# proper.net
KiCad netlist of a schematic drawn in EAGLE
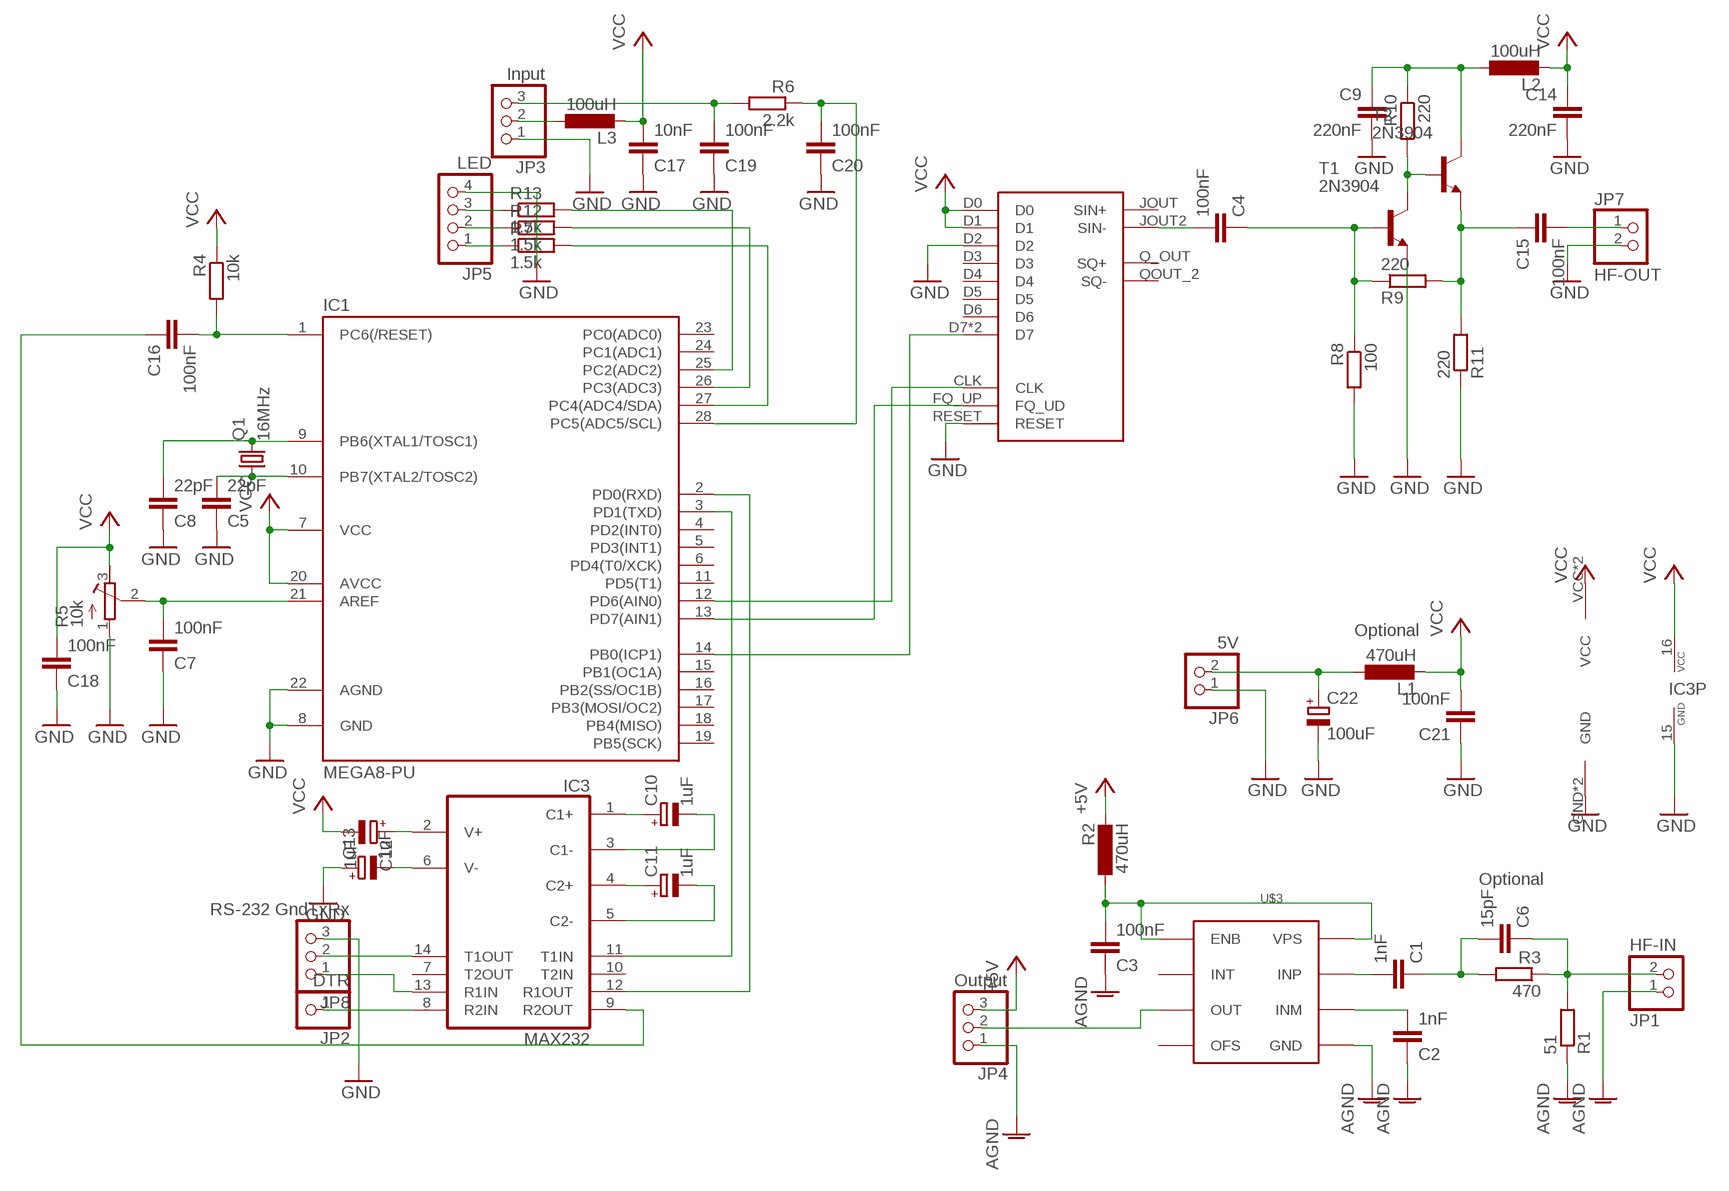
[diagram p0: schematic, sheet 1]

(export (version "E")
  (design (tool "Eeschema 10.0.6"))
  (components
    (comp (ref "C1")
      (value "1nF")
      (footprint "eagle-import:C025-025X050")
      (libsource (lib "eagle-import") (part "C-EU025-025X050"))
    )
    (comp (ref "C2")
      (value "1nF")
      (footprint "eagle-import:C025-025X050")
      (libsource (lib "eagle-import") (part "C-EU025-025X050"))
    )
    (comp (ref "C3")
      (value "100nF")
      (footprint "eagle-import:C025-025X050")
      (libsource (lib "eagle-import") (part "C-EU025-025X050"))
    )
    (comp (ref "C4")
      (value "100nF")
      (footprint "eagle-import:C025-025X050")
      (libsource (lib "eagle-import") (part "C-EU025-025X050"))
    )
    (comp (ref "C5")
      (value "22pF")
      (footprint "eagle-import:C102-043X133")
      (libsource (lib "eagle-import") (part "C-EU102-043X133"))
    )
    (comp (ref "C6")
      (value "15pF")
      (footprint "eagle-import:C050-025X075")
      (libsource (lib "eagle-import") (part "C-EU050-025X075"))
    )
    (comp (ref "C7")
      (value "100nF")
      (footprint "eagle-import:C025-025X050")
      (libsource (lib "eagle-import") (part "C-EU025-025X050"))
    )
    (comp (ref "C8")
      (value "22pF")
      (footprint "eagle-import:C025-025X050")
      (libsource (lib "eagle-import") (part "C-EU025-025X050"))
    )
    (comp (ref "C9")
      (value "220nF")
      (footprint "eagle-import:C025-025X050")
      (libsource (lib "eagle-import") (part "C-EU025-025X050"))
    )
    (comp (ref "C10")
      (value "1uF")
      (footprint "eagle-import:E2,5-5")
      (libsource (lib "eagle-import") (part "CPOL-EUE2.5-5"))
    )
    (comp (ref "C11")
      (value "1uF")
      (footprint "eagle-import:E2,5-5")
      (libsource (lib "eagle-import") (part "CPOL-EUE2.5-5"))
    )
    (comp (ref "C12")
      (value "1uF")
      (footprint "eagle-import:E2,5-5")
      (libsource (lib "eagle-import") (part "CPOL-EUE2.5-5"))
    )
    (comp (ref "C13")
      (value "1uF")
      (footprint "eagle-import:E2,5-5")
      (libsource (lib "eagle-import") (part "CPOL-EUE2.5-5"))
    )
    (comp (ref "C14")
      (value "220nF")
      (footprint "eagle-import:C050-025X075")
      (libsource (lib "eagle-import") (part "C-EU050-025X075"))
    )
    (comp (ref "C15")
      (value "100nF")
      (footprint "eagle-import:C050-025X075")
      (libsource (lib "eagle-import") (part "C-EU050-025X075"))
    )
    (comp (ref "C16")
      (value "100nF")
      (footprint "eagle-import:C075-032X103")
      (libsource (lib "eagle-import") (part "C-EU075-032X103"))
    )
    (comp (ref "C17")
      (value "10nF")
      (footprint "eagle-import:C025-025X050")
      (libsource (lib "eagle-import") (part "C-EU025-025X050"))
    )
    (comp (ref "C18")
      (value "100nF")
      (footprint "eagle-import:C050-025X075")
      (libsource (lib "eagle-import") (part "C-EU050-025X075"))
    )
    (comp (ref "C19")
      (value "100nF")
      (footprint "eagle-import:C025-025X050")
      (libsource (lib "eagle-import") (part "C-EU025-025X050"))
    )
    (comp (ref "C20")
      (value "100nF")
      (footprint "eagle-import:C025-025X050")
      (libsource (lib "eagle-import") (part "C-EU025-025X050"))
    )
    (comp (ref "C21")
      (value "100nF")
      (footprint "eagle-import:C025-025X050")
      (libsource (lib "eagle-import") (part "C-EU025-025X050"))
    )
    (comp (ref "C22")
      (value "100uF")
      (footprint "eagle-import:E2,5-6")
      (libsource (lib "eagle-import") (part "CPOL-EUE2.5-6"))
    )
    (comp (ref "IC1")
      (value "MEGA8-PU")
      (footprint "eagle-import:DIL28-3")
      (libsource (lib "eagle-import") (part "MEGA8-PU"))
    )
    (comp (ref "IC3")
      (value "MAX232")
      (footprint "eagle-import:DIL16")
      (fields (field (name "MF") "MAXIM") (field (name "MPN") "MAX232ACPE+"))
      (libsource (lib "eagle-import") (part "MAX232"))
    )
    (comp (ref "JP1")
      (value "HF-IN")
      (footprint "eagle-import:1X02")
      (libsource (lib "eagle-import") (part "PINHD-1X2"))
    )
    (comp (ref "JP2")
      (value "DTR")
      (footprint "eagle-import:1X01")
      (libsource (lib "eagle-import") (part "PINHD-1X1"))
    )
    (comp (ref "JP3")
      (value "Input")
      (footprint "eagle-import:1X03")
      (libsource (lib "eagle-import") (part "PINHD-1X3"))
    )
    (comp (ref "JP4")
      (value "Output")
      (footprint "eagle-import:1X03")
      (libsource (lib "eagle-import") (part "PINHD-1X3"))
    )
    (comp (ref "JP5")
      (value "LED")
      (footprint "eagle-import:1X04")
      (libsource (lib "eagle-import") (part "PINHD-1X4"))
    )
    (comp (ref "JP6")
      (value "5V")
      (footprint "eagle-import:1X02")
      (libsource (lib "eagle-import") (part "PINHD-1X2"))
    )
    (comp (ref "JP7")
      (value "HF-OUT")
      (footprint "eagle-import:1X02")
      (libsource (lib "eagle-import") (part "PINHD-1X2"))
    )
    (comp (ref "JP8")
      (value "RS-232 GndTxRx")
      (footprint "eagle-import:1X03")
      (libsource (lib "eagle-import") (part "PINHD-1X3"))
    )
    (comp (ref "L1")
      (value "470uH")
      (footprint "eagle-import:0207_5V")
      (libsource (lib "eagle-import") (part "L-EU0207/5V"))
    )
    (comp (ref "L2")
      (value "100uH")
      (footprint "eagle-import:0207_12")
      (libsource (lib "eagle-import") (part "L-EU0207/12"))
    )
    (comp (ref "L3")
      (value "100uH")
      (footprint "eagle-import:0207_2V")
      (libsource (lib "eagle-import") (part "L-EU0207/2V"))
    )
    (comp (ref "Q1")
      (value "16MHz")
      (footprint "eagle-import:HC49U-V")
      (libsource (lib "eagle-import") (part "CRYSTALHC49U-V"))
    )
    (comp (ref "R1")
      (value "51")
      (footprint "eagle-import:0204V")
      (libsource (lib "eagle-import") (part "R-EU_0204/2V"))
    )
    (comp (ref "R2")
      (value "470uH")
      (footprint "eagle-import:0204_5")
      (libsource (lib "eagle-import") (part "L-EU0204/5"))
    )
    (comp (ref "R3")
      (value "470")
      (footprint "eagle-import:0204_5")
      (libsource (lib "eagle-import") (part "R-EU_0204/5"))
    )
    (comp (ref "R4")
      (value "10k")
      (footprint "eagle-import:0204_5")
      (libsource (lib "eagle-import") (part "R-EU_0204/5"))
    )
    (comp (ref "R5")
      (value "10k")
      (footprint "eagle-import:RTRIM64W")
      (libsource (lib "eagle-import") (part "R-TRIMM64W"))
    )
    (comp (ref "R6")
      (value "2.2k")
      (footprint "eagle-import:0204V")
      (libsource (lib "eagle-import") (part "R-EU_0204/2V"))
    )
    (comp (ref "R7")
      (value "1.5k")
      (footprint "eagle-import:0204_5")
      (libsource (lib "eagle-import") (part "R-EU_0204/5"))
    )
    (comp (ref "R8")
      (value "100")
      (footprint "eagle-import:0204V")
      (libsource (lib "eagle-import") (part "R-EU_0204/2V"))
    )
    (comp (ref "R9")
      (value "220")
      (footprint "eagle-import:0204V")
      (libsource (lib "eagle-import") (part "R-EU_0204/2V"))
    )
    (comp (ref "R10")
      (value "220")
      (footprint "eagle-import:0204V")
      (libsource (lib "eagle-import") (part "R-EU_0204/2V"))
    )
    (comp (ref "R11")
      (value "220")
      (footprint "eagle-import:0204V")
      (libsource (lib "eagle-import") (part "R-EU_0204/2V"))
    )
    (comp (ref "R12")
      (value "1.5k")
      (footprint "eagle-import:0204_5")
      (libsource (lib "eagle-import") (part "R-EU_0204/5"))
    )
    (comp (ref "R13")
      (value "1.5k")
      (footprint "eagle-import:0204_5")
      (libsource (lib "eagle-import") (part "R-EU_0204/5"))
    )
    (comp (ref "T1")
      (value "2N3904")
      (footprint "eagle-import:TO92-EBC")
      (libsource (lib "eagle-import") (part "-NPN-TO92-EBC2N3904"))
    )
    (comp (ref "T2")
      (value "2N3904")
      (footprint "eagle-import:TO92-EBC")
      (libsource (lib "eagle-import") (part "-NPN-TO92-EBC2N3904"))
    )
    (comp (ref "U$1")
      (value "DDS-1")
      (footprint "eagle-import:DDS-1")
      (libsource (lib "eagle-import") (part "DDS-1"))
    )
    (comp (ref "U$3")
      (value "AD8307")
      (footprint "eagle-import:DIL08")
      (libsource (lib "eagle-import") (part "AD8307"))
    )
  )
  (nets
    (net (code "1") (name "+5V") (class "Default")
      (node (ref "JP4") (pin "3") (pinfunction "3_3") (pintype "passive"))
      (node (ref "R2") (pin "2") (pinfunction "2_2") (pintype "passive"))
    )
    (net (code "2") (name "AGND") (class "Default")
      (node (ref "C2") (pin "1") (pinfunction "1_1") (pintype "passive"))
      (node (ref "C3") (pin "1") (pinfunction "1_1") (pintype "passive"))
      (node (ref "JP1") (pin "1") (pinfunction "1_1") (pintype "passive"))
      (node (ref "JP4") (pin "1") (pinfunction "1_1") (pintype "passive"))
      (node (ref "R1") (pin "1") (pinfunction "1_1") (pintype "passive"))
      (node (ref "U$3") (pin "2") (pinfunction "GND_2") (pintype "bidirectional"))
    )
    (net (code "3") (name "GND") (class "Default")
      (node (ref "C13") (pin "+") (pinfunction "+_+") (pintype "passive"))
      (node (ref "C14") (pin "2") (pinfunction "2_2") (pintype "passive"))
      (node (ref "C17") (pin "1") (pinfunction "1_1") (pintype "passive"))
      (node (ref "C18") (pin "1") (pinfunction "1_1") (pintype "passive"))
      (node (ref "C19") (pin "1") (pinfunction "1_1") (pintype "passive"))
      (node (ref "C20") (pin "1") (pinfunction "1_1") (pintype "passive"))
      (node (ref "C21") (pin "1") (pinfunction "1_1") (pintype "passive"))
      (node (ref "C22") (pin "-") (pinfunction "-_-") (pintype "passive"))
      (node (ref "C5") (pin "1") (pinfunction "1_1") (pintype "passive"))
      (node (ref "C7") (pin "1") (pinfunction "1_1") (pintype "passive"))
      (node (ref "C8") (pin "1") (pinfunction "1_1") (pintype "passive"))
      (node (ref "C9") (pin "2") (pinfunction "2_2") (pintype "passive"))
      (node (ref "IC1") (pin "22") (pinfunction "AGND_22") (pintype "power_in"))
      (node (ref "IC1") (pin "8") (pinfunction "GND_8") (pintype "power_in"))
      (node (ref "IC3") (pin "15") (pinfunction "GND_15") (pintype "power_in"))
      (node (ref "JP3") (pin "1") (pinfunction "1_1") (pintype "passive"))
      (node (ref "JP5") (pin "4") (pinfunction "4_4") (pintype "passive"))
      (node (ref "JP6") (pin "1") (pinfunction "1_1") (pintype "passive"))
      (node (ref "JP7") (pin "2") (pinfunction "2_2") (pintype "passive"))
      (node (ref "JP8") (pin "3") (pinfunction "3_3") (pintype "passive"))
      (node (ref "R11") (pin "1") (pinfunction "1_1") (pintype "passive"))
      (node (ref "R5") (pin "1") (pinfunction "A_1") (pintype "passive"))
      (node (ref "R8") (pin "2") (pinfunction "2_2") (pintype "passive"))
      (node (ref "T1") (pin "E") (pinfunction "E_E") (pintype "passive"))
      (node (ref "U$1") (pin "D2") (pinfunction "D2_D2") (pintype "bidirectional"))
      (node (ref "U$1") (pin "GND") (pinfunction "GND_GND") (pintype "bidirectional"))
      (node (ref "U$1") (pin "GND2") (pinfunction "GND_GND2") (pintype "bidirectional"))
      (node (ref "U$1") (pin "RESET") (pinfunction "RESET_RESET") (pintype "bidirectional"))
    )
    (net (code "4") (name "Net-(C1-Pad1)") (class "Default")
      (node (ref "C1") (pin "1") (pinfunction "1_1") (pintype "passive"))
      (node (ref "C6") (pin "2") (pinfunction "2_2") (pintype "passive"))
      (node (ref "R3") (pin "2") (pinfunction "2_2") (pintype "passive"))
    )
    (net (code "5") (name "Net-(C4-Pad1)") (class "Default")
      (node (ref "C4") (pin "1") (pinfunction "1_1") (pintype "passive"))
      (node (ref "R8") (pin "1") (pinfunction "1_1") (pintype "passive"))
      (node (ref "R9") (pin "1") (pinfunction "1_1") (pintype "passive"))
      (node (ref "T1") (pin "B") (pinfunction "B_B") (pintype "passive"))
    )
    (net (code "6") (name "Net-(C6-Pad1)") (class "Default")
      (node (ref "C6") (pin "1") (pinfunction "1_1") (pintype "passive"))
      (node (ref "JP1") (pin "2") (pinfunction "2_2") (pintype "passive"))
      (node (ref "R1") (pin "2") (pinfunction "2_2") (pintype "passive"))
      (node (ref "R3") (pin "1") (pinfunction "1_1") (pintype "passive"))
    )
    (net (code "7") (name "Net-(C9-Pad1)") (class "Default")
      (node (ref "C9") (pin "1") (pinfunction "1_1") (pintype "passive"))
      (node (ref "L2") (pin "1") (pinfunction "1_1") (pintype "passive"))
      (node (ref "R10") (pin "1") (pinfunction "1_1") (pintype "passive"))
      (node (ref "T2") (pin "C") (pinfunction "C_C") (pintype "passive"))
    )
    (net (code "8") (name "Net-(C15-Pad1)") (class "Default")
      (node (ref "C15") (pin "1") (pinfunction "1_1") (pintype "passive"))
      (node (ref "R11") (pin "2") (pinfunction "2_2") (pintype "passive"))
      (node (ref "R9") (pin "2") (pinfunction "2_2") (pintype "passive"))
      (node (ref "T2") (pin "E") (pinfunction "E_E") (pintype "passive"))
    )
    (net (code "9") (name "Net-(C15-Pad2)") (class "Default")
      (node (ref "C15") (pin "2") (pinfunction "2_2") (pintype "passive"))
      (node (ref "JP7") (pin "1") (pinfunction "1_1") (pintype "passive"))
    )
    (net (code "10") (name "Net-(C19-Pad2)") (class "Default")
      (node (ref "C19") (pin "2") (pinfunction "2_2") (pintype "passive"))
      (node (ref "JP3") (pin "3") (pinfunction "3_3") (pintype "passive"))
      (node (ref "R6") (pin "2") (pinfunction "2_2") (pintype "passive"))
    )
    (net (code "11") (name "Net-(C22-Pad+)") (class "Default")
      (node (ref "C22") (pin "+") (pinfunction "+_+") (pintype "passive"))
      (node (ref "JP6") (pin "2") (pinfunction "2_2") (pintype "passive"))
      (node (ref "L1") (pin "1") (pinfunction "1_1") (pintype "passive"))
    )
    (net (code "12") (name "Net-(IC1-AREF)") (class "Default")
      (node (ref "C7") (pin "2") (pinfunction "2_2") (pintype "passive"))
      (node (ref "IC1") (pin "21") (pinfunction "AREF_21") (pintype "passive"))
      (node (ref "R5") (pin "2") (pinfunction "S_2") (pintype "passive"))
    )
    (net (code "13") (name "Net-(IC1-PB0(ICP1))") (class "Default")
      (node (ref "IC1") (pin "14") (pinfunction "PB0(ICP1)_14") (pintype "bidirectional"))
      (node (ref "U$1") (pin "D7") (pinfunction "D7_D7") (pintype "bidirectional"))
      (node (ref "U$1") (pin "D7_2") (pinfunction "D7_D7_2") (pintype "bidirectional"))
    )
    (net (code "14") (name "Net-(IC1-PB6(XTAL1{slash}TOSC1))") (class "Default")
      (node (ref "C8") (pin "2") (pinfunction "2_2") (pintype "passive"))
      (node (ref "IC1") (pin "9") (pinfunction "PB6(XTAL1/TOSC1)_9") (pintype "bidirectional"))
      (node (ref "Q1") (pin "2") (pinfunction "2_2") (pintype "passive"))
    )
    (net (code "15") (name "Net-(IC1-PB7(XTAL2{slash}TOSC2))") (class "Default")
      (node (ref "C5") (pin "2") (pinfunction "2_2") (pintype "passive"))
      (node (ref "IC1") (pin "10") (pinfunction "PB7(XTAL2/TOSC2)_10") (pintype "bidirectional"))
      (node (ref "Q1") (pin "1") (pinfunction "1_1") (pintype "passive"))
    )
    (net (code "16") (name "Net-(IC1-PC2(ADC2))") (class "Default")
      (node (ref "IC1") (pin "25") (pinfunction "PC2(ADC2)_25") (pintype "bidirectional"))
      (node (ref "R13") (pin "2") (pinfunction "2_2") (pintype "passive"))
    )
    (net (code "17") (name "Net-(IC1-PC3(ADC3))") (class "Default")
      (node (ref "IC1") (pin "26") (pinfunction "PC3(ADC3)_26") (pintype "bidirectional"))
      (node (ref "R12") (pin "2") (pinfunction "2_2") (pintype "passive"))
    )
    (net (code "18") (name "Net-(IC1-PC4(ADC4{slash}SDA))") (class "Default")
      (node (ref "IC1") (pin "27") (pinfunction "PC4(ADC4/SDA)_27") (pintype "bidirectional"))
      (node (ref "R7") (pin "2") (pinfunction "2_2") (pintype "passive"))
    )
    (net (code "19") (name "Net-(IC1-PC5(ADC5{slash}SCL))") (class "Default")
      (node (ref "C20") (pin "2") (pinfunction "2_2") (pintype "passive"))
      (node (ref "IC1") (pin "28") (pinfunction "PC5(ADC5/SCL)_28") (pintype "bidirectional"))
      (node (ref "R6") (pin "1") (pinfunction "1_1") (pintype "passive"))
    )
    (net (code "20") (name "Net-(IC1-PC6({slash}RESET))") (class "Default")
      (node (ref "C16") (pin "2") (pinfunction "2_2") (pintype "passive"))
      (node (ref "IC1") (pin "1") (pinfunction "PC6(/RESET)_1") (pintype "bidirectional"))
      (node (ref "R4") (pin "2") (pinfunction "2_2") (pintype "passive"))
    )
    (net (code "21") (name "Net-(IC1-PD0(RXD))") (class "Default")
      (node (ref "IC1") (pin "2") (pinfunction "PD0(RXD)_2") (pintype "bidirectional"))
      (node (ref "IC3") (pin "12") (pinfunction "R1OUT_12") (pintype "output"))
    )
    (net (code "22") (name "Net-(IC1-PD1(TXD))") (class "Default")
      (node (ref "IC1") (pin "3") (pinfunction "PD1(TXD)_3") (pintype "bidirectional"))
      (node (ref "IC3") (pin "11") (pinfunction "T1IN_11") (pintype "input"))
    )
    (net (code "23") (name "Net-(IC1-PD6(AIN0))") (class "Default")
      (node (ref "IC1") (pin "12") (pinfunction "PD6(AIN0)_12") (pintype "bidirectional"))
      (node (ref "U$1") (pin "CLK") (pinfunction "CLK_CLK") (pintype "bidirectional"))
    )
    (net (code "24") (name "Net-(IC1-PD7(AIN1))") (class "Default")
      (node (ref "IC1") (pin "13") (pinfunction "PD7(AIN1)_13") (pintype "bidirectional"))
      (node (ref "U$1") (pin "FQ_UP") (pinfunction "FQ_UD_FQ_UP") (pintype "bidirectional"))
    )
    (net (code "25") (name "Net-(IC3A-C1+)") (class "Default")
      (node (ref "C10") (pin "+") (pinfunction "+_+") (pintype "passive"))
      (node (ref "IC3") (pin "1") (pinfunction "C1+_1") (pintype "bidirectional"))
    )
    (net (code "26") (name "Net-(IC3A-C1-)") (class "Default")
      (node (ref "C10") (pin "-") (pinfunction "-_-") (pintype "passive"))
      (node (ref "IC3") (pin "3") (pinfunction "C1-_3") (pintype "bidirectional"))
    )
    (net (code "27") (name "Net-(IC3A-C2+)") (class "Default")
      (node (ref "C11") (pin "+") (pinfunction "+_+") (pintype "passive"))
      (node (ref "IC3") (pin "4") (pinfunction "C2+_4") (pintype "bidirectional"))
    )
    (net (code "28") (name "Net-(IC3A-C2-)") (class "Default")
      (node (ref "C11") (pin "-") (pinfunction "-_-") (pintype "passive"))
      (node (ref "IC3") (pin "5") (pinfunction "C2-_5") (pintype "bidirectional"))
    )
    (net (code "29") (name "Net-(IC3A-R1IN)") (class "Default")
      (node (ref "IC3") (pin "13") (pinfunction "R1IN_13") (pintype "input"))
      (node (ref "JP8") (pin "1") (pinfunction "1_1") (pintype "passive"))
    )
    (net (code "30") (name "Net-(IC3A-R2IN)") (class "Default")
      (node (ref "IC3") (pin "8") (pinfunction "R2IN_8") (pintype "input"))
      (node (ref "JP2") (pin "1") (pinfunction "1_1") (pintype "passive"))
    )
    (net (code "31") (name "Net-(IC3A-R2OUT)") (class "Default")
      (node (ref "C16") (pin "1") (pinfunction "1_1") (pintype "passive"))
      (node (ref "IC3") (pin "9") (pinfunction "R2OUT_9") (pintype "output"))
    )
    (net (code "32") (name "Net-(IC3A-T1OUT)") (class "Default")
      (node (ref "IC3") (pin "14") (pinfunction "T1OUT_14") (pintype "output"))
      (node (ref "JP8") (pin "2") (pinfunction "2_2") (pintype "passive"))
    )
    (net (code "33") (name "Net-(IC3A-V+)") (class "Default")
      (node (ref "C12") (pin "+") (pinfunction "+_+") (pintype "passive"))
      (node (ref "IC3") (pin "2") (pinfunction "V+_2") (pintype "bidirectional"))
    )
    (net (code "34") (name "Net-(IC3A-V-)") (class "Default")
      (node (ref "C13") (pin "-") (pinfunction "-_-") (pintype "passive"))
      (node (ref "IC3") (pin "6") (pinfunction "V-_6") (pintype "bidirectional"))
    )
    (net (code "35") (name "Net-(JP3-Pad2)") (class "Default")
      (node (ref "JP3") (pin "2") (pinfunction "2_2") (pintype "passive"))
      (node (ref "L3") (pin "1") (pinfunction "1_1") (pintype "passive"))
    )
    (net (code "36") (name "Net-(JP5-Pad1)") (class "Default")
      (node (ref "JP5") (pin "1") (pinfunction "1_1") (pintype "passive"))
      (node (ref "R7") (pin "1") (pinfunction "1_1") (pintype "passive"))
    )
    (net (code "37") (name "Net-(JP5-Pad2)") (class "Default")
      (node (ref "JP5") (pin "2") (pinfunction "2_2") (pintype "passive"))
      (node (ref "R12") (pin "1") (pinfunction "1_1") (pintype "passive"))
    )
    (net (code "38") (name "Net-(JP5-Pad3)") (class "Default")
      (node (ref "JP5") (pin "3") (pinfunction "3_3") (pintype "passive"))
      (node (ref "R13") (pin "1") (pinfunction "1_1") (pintype "passive"))
    )
    (net (code "39") (name "Net-(R10-Pad2)") (class "Default")
      (node (ref "R10") (pin "2") (pinfunction "2_2") (pintype "passive"))
      (node (ref "T1") (pin "C") (pinfunction "C_C") (pintype "passive"))
      (node (ref "T2") (pin "B") (pinfunction "B_B") (pintype "passive"))
    )
    (net (code "40") (name "Net-(U$1A-SIN-)") (class "Default")
      (node (ref "C4") (pin "2") (pinfunction "2_2") (pintype "passive"))
      (node (ref "U$1") (pin "JOUT2") (pinfunction "SIN-_JOUT2") (pintype "bidirectional"))
    )
    (net (code "41") (name "Net-(U$3-ENB)") (class "Default")
      (node (ref "C3") (pin "2") (pinfunction "2_2") (pintype "passive"))
      (node (ref "R2") (pin "1") (pinfunction "1_1") (pintype "passive"))
      (node (ref "U$3") (pin "6") (pinfunction "ENB_6") (pintype "bidirectional"))
      (node (ref "U$3") (pin "7") (pinfunction "VPS_7") (pintype "bidirectional"))
    )
    (net (code "42") (name "Net-(U$3-INM)") (class "Default")
      (node (ref "C2") (pin "2") (pinfunction "2_2") (pintype "passive"))
      (node (ref "U$3") (pin "1") (pinfunction "INM_1") (pintype "bidirectional"))
    )
    (net (code "43") (name "Net-(U$3-INP)") (class "Default")
      (node (ref "C1") (pin "2") (pinfunction "2_2") (pintype "passive"))
      (node (ref "U$3") (pin "8") (pinfunction "INP_8") (pintype "bidirectional"))
    )
    (net (code "44") (name "Net-(U$3-OUT)") (class "Default")
      (node (ref "JP4") (pin "2") (pinfunction "2_2") (pintype "passive"))
      (node (ref "U$3") (pin "4") (pinfunction "OUT_4") (pintype "bidirectional"))
    )
    (net (code "45") (name "VCC") (class "Default")
      (node (ref "C12") (pin "-") (pinfunction "-_-") (pintype "passive"))
      (node (ref "C14") (pin "1") (pinfunction "1_1") (pintype "passive"))
      (node (ref "C17") (pin "2") (pinfunction "2_2") (pintype "passive"))
      (node (ref "C18") (pin "2") (pinfunction "2_2") (pintype "passive"))
      (node (ref "C21") (pin "2") (pinfunction "2_2") (pintype "passive"))
      (node (ref "IC1") (pin "20") (pinfunction "AVCC_20") (pintype "passive"))
      (node (ref "IC1") (pin "7") (pinfunction "VCC_7") (pintype "power_in"))
      (node (ref "IC3") (pin "16") (pinfunction "VCC_16") (pintype "power_in"))
      (node (ref "L1") (pin "2") (pinfunction "2_2") (pintype "passive"))
      (node (ref "L2") (pin "2") (pinfunction "2_2") (pintype "passive"))
      (node (ref "L3") (pin "2") (pinfunction "2_2") (pintype "passive"))
      (node (ref "R4") (pin "1") (pinfunction "1_1") (pintype "passive"))
      (node (ref "R5") (pin "3") (pinfunction "E_3") (pintype "passive"))
      (node (ref "U$1") (pin "D0") (pinfunction "D0_D0") (pintype "bidirectional"))
      (node (ref "U$1") (pin "D1") (pinfunction "D1_D1") (pintype "bidirectional"))
      (node (ref "U$1") (pin "VCC") (pinfunction "VCC_VCC") (pintype "bidirectional"))
      (node (ref "U$1") (pin "VCC2") (pinfunction "VCC_VCC2") (pintype "bidirectional"))
    )
    (net (code "46") (name "unconnected-(IC1-PB1(OC1A)-Pad15)") (class "Default")
      (node (ref "IC1") (pin "15") (pinfunction "PB1(OC1A)_15") (pintype "bidirectional"))
    )
    (net (code "47") (name "unconnected-(IC1-PB2(SS{slash}OC1B)-Pad16)") (class "Default")
      (node (ref "IC1") (pin "16") (pinfunction "PB2(SS/OC1B)_16") (pintype "bidirectional"))
    )
    (net (code "48") (name "unconnected-(IC1-PB3(MOSI{slash}OC2)-Pad17)") (class "Default")
      (node (ref "IC1") (pin "17") (pinfunction "PB3(MOSI/OC2)_17") (pintype "bidirectional"))
    )
    (net (code "49") (name "unconnected-(IC1-PB4(MISO)-Pad18)") (class "Default")
      (node (ref "IC1") (pin "18") (pinfunction "PB4(MISO)_18") (pintype "bidirectional"))
    )
    (net (code "50") (name "unconnected-(IC1-PB5(SCK)-Pad19)") (class "Default")
      (node (ref "IC1") (pin "19") (pinfunction "PB5(SCK)_19") (pintype "bidirectional"))
    )
    (net (code "51") (name "unconnected-(IC1-PC0(ADC0)-Pad23)") (class "Default")
      (node (ref "IC1") (pin "23") (pinfunction "PC0(ADC0)_23") (pintype "bidirectional"))
    )
    (net (code "52") (name "unconnected-(IC1-PC1(ADC1)-Pad24)") (class "Default")
      (node (ref "IC1") (pin "24") (pinfunction "PC1(ADC1)_24") (pintype "bidirectional"))
    )
    (net (code "53") (name "unconnected-(IC1-PD2(INT0)-Pad4)") (class "Default")
      (node (ref "IC1") (pin "4") (pinfunction "PD2(INT0)_4") (pintype "bidirectional"))
    )
    (net (code "54") (name "unconnected-(IC1-PD3(INT1)-Pad5)") (class "Default")
      (node (ref "IC1") (pin "5") (pinfunction "PD3(INT1)_5") (pintype "bidirectional"))
    )
    (net (code "55") (name "unconnected-(IC1-PD4(T0{slash}XCK)-Pad6)") (class "Default")
      (node (ref "IC1") (pin "6") (pinfunction "PD4(T0/XCK)_6") (pintype "bidirectional"))
    )
    (net (code "56") (name "unconnected-(IC1-PD5(T1)-Pad11)") (class "Default")
      (node (ref "IC1") (pin "11") (pinfunction "PD5(T1)_11") (pintype "bidirectional"))
    )
    (net (code "57") (name "unconnected-(IC3A-T2IN-Pad10)") (class "Default")
      (node (ref "IC3") (pin "10") (pinfunction "T2IN_10") (pintype "input"))
    )
    (net (code "58") (name "unconnected-(IC3A-T2OUT-Pad7)") (class "Default")
      (node (ref "IC3") (pin "7") (pinfunction "T2OUT_7") (pintype "output"))
    )
    (net (code "59") (name "unconnected-(U$1-PadD3)") (class "Default")
      (node (ref "U$1") (pin "D3") (pinfunction "D3_D3") (pintype "bidirectional"))
    )
    (net (code "60") (name "unconnected-(U$1-PadD4)") (class "Default")
      (node (ref "U$1") (pin "D4") (pinfunction "D4_D4") (pintype "bidirectional"))
    )
    (net (code "61") (name "unconnected-(U$1-PadD5)") (class "Default")
      (node (ref "U$1") (pin "D5") (pinfunction "D5_D5") (pintype "bidirectional"))
    )
    (net (code "62") (name "unconnected-(U$1-PadD6)") (class "Default")
      (node (ref "U$1") (pin "D6") (pinfunction "D6_D6") (pintype "bidirectional"))
    )
    (net (code "63") (name "unconnected-(U$1A-SIN+-PadJOUT)") (class "Default")
      (node (ref "U$1") (pin "JOUT") (pinfunction "SIN+_JOUT") (pintype "bidirectional"))
    )
    (net (code "64") (name "unconnected-(U$1A-SQ+-PadQ_OUT)") (class "Default")
      (node (ref "U$1") (pin "Q_OUT") (pinfunction "SQ+_Q_OUT") (pintype "bidirectional"))
    )
    (net (code "65") (name "unconnected-(U$1A-SQ--PadQOUT_2)") (class "Default")
      (node (ref "U$1") (pin "QOUT_2") (pinfunction "SQ-_QOUT_2") (pintype "bidirectional"))
    )
    (net (code "66") (name "unconnected-(U$3-INT-Pad5)") (class "Default")
      (node (ref "U$3") (pin "5") (pinfunction "INT_5") (pintype "bidirectional"))
    )
    (net (code "67") (name "unconnected-(U$3-OFS-Pad3)") (class "Default")
      (node (ref "U$3") (pin "3") (pinfunction "OFS_3") (pintype "bidirectional"))
    )
  )
)
